# master.net
KiCad netlist of a schematic drawn in EAGLE
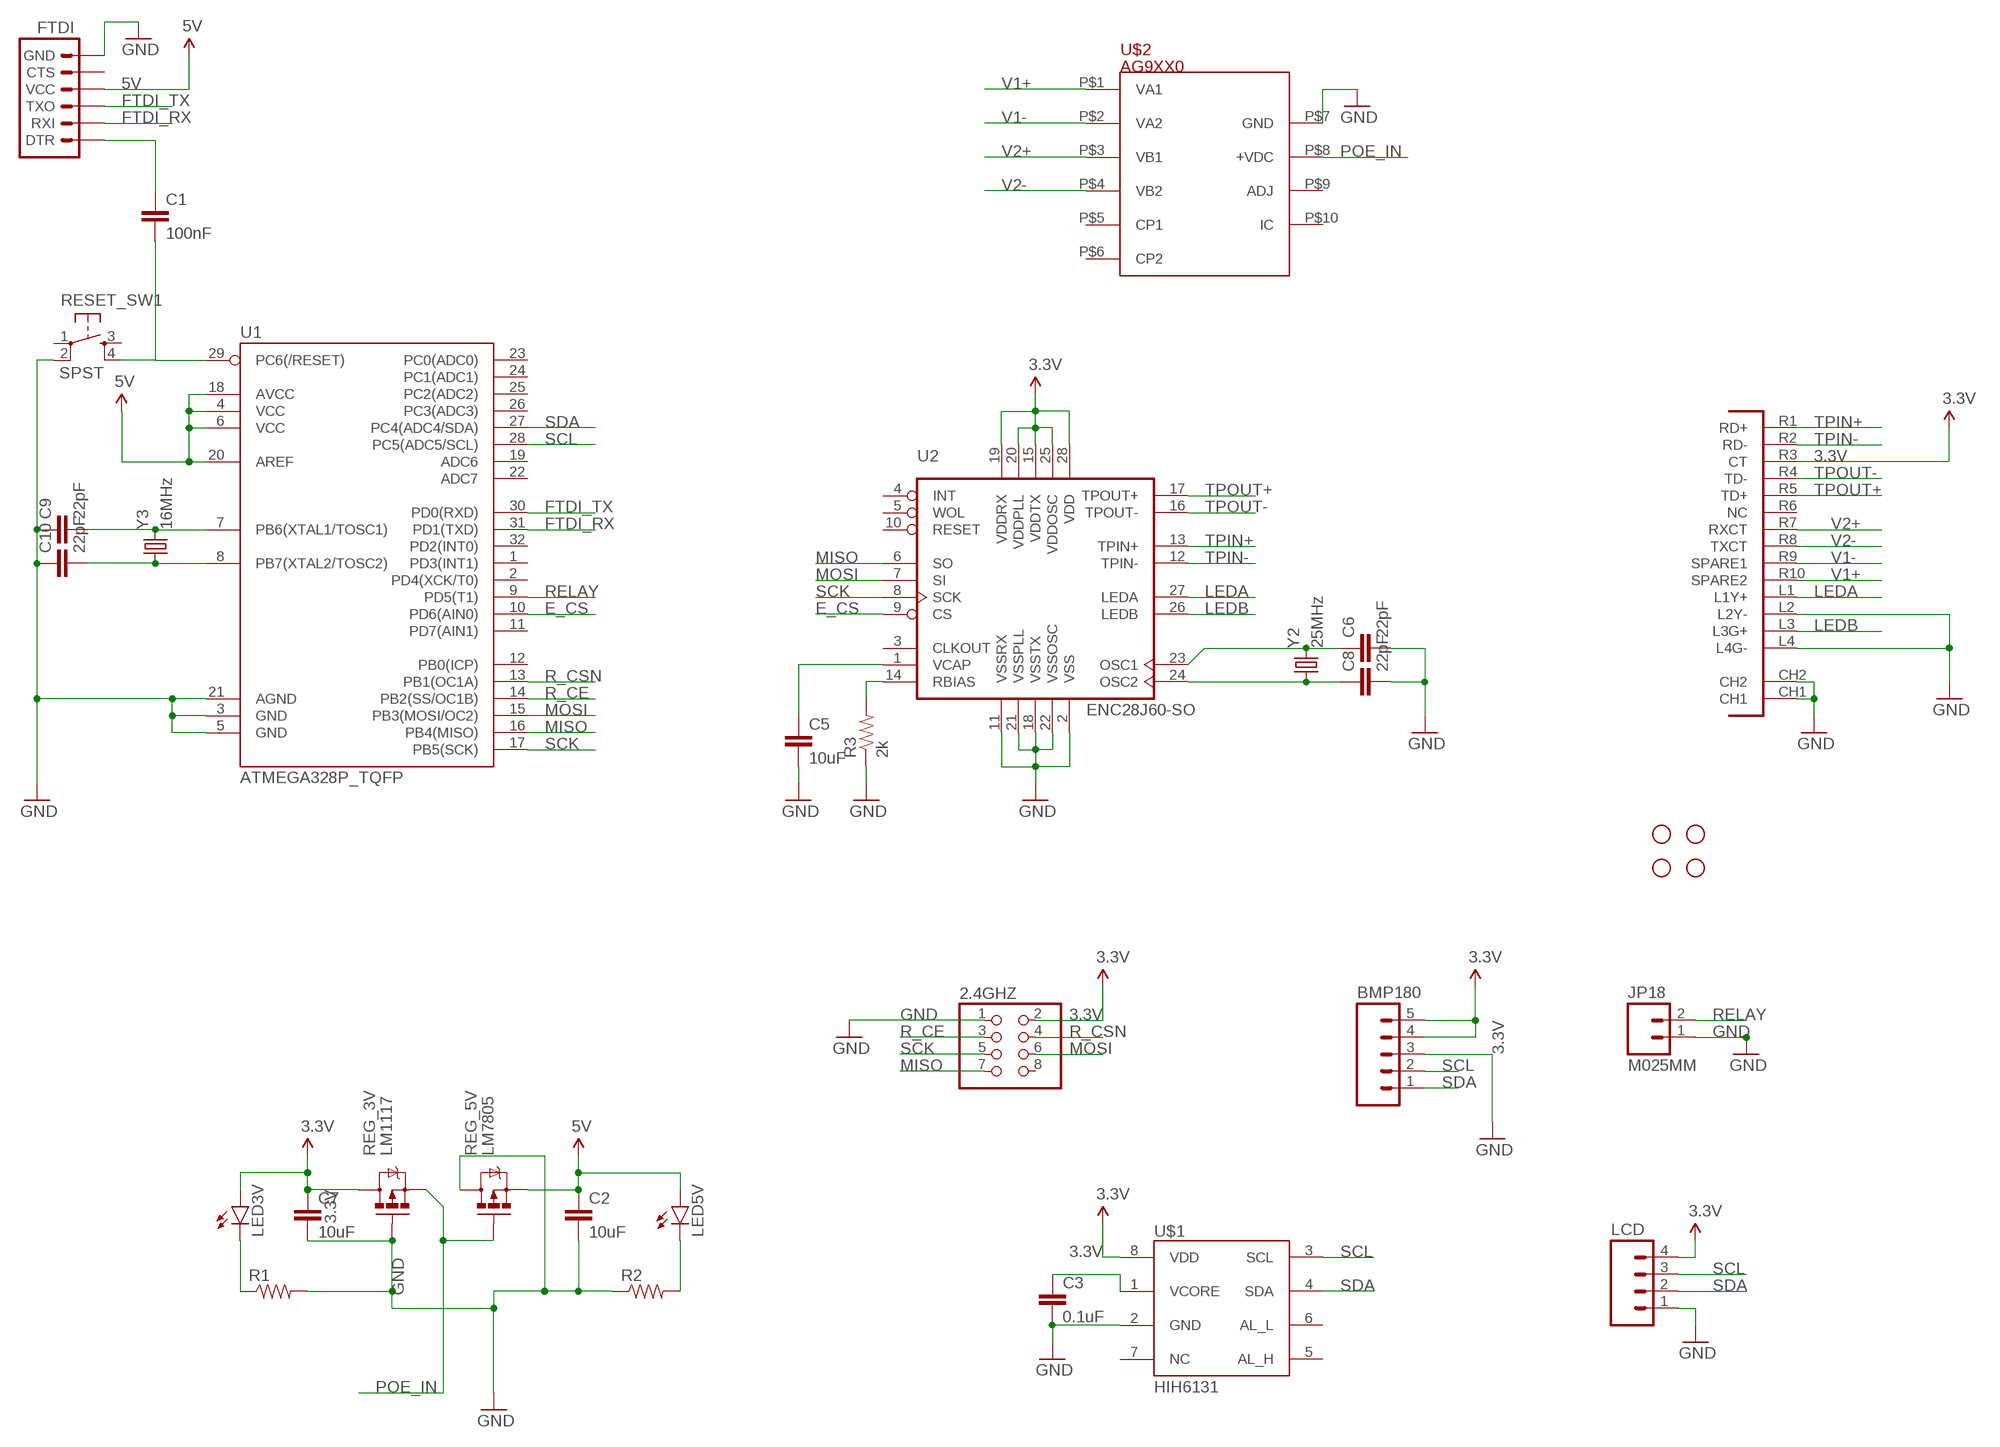
[diagram p0: schematic, sheet 1]

(export (version "E")
  (design (tool "Eeschema 10.0.6"))
  (components
    (comp (ref "2.4GHZ")
      (value "PINHD-2X4")
      (footprint "eagle-import:2X04")
      (libsource (lib "eagle-import") (part "PINHD-2X4"))
    )
    (comp (ref "BMP180")
      (value "M05PTH")
      (footprint "eagle-import:1X05")
      (libsource (lib "eagle-import") (part "M05PTH"))
    )
    (comp (ref "C1")
      (value "100nF")
      (footprint "eagle-import:CAP-PTH-SMALL")
      (libsource (lib "eagle-import") (part "CAPPTH"))
    )
    (comp (ref "C2")
      (value "10uF")
      (footprint "eagle-import:CAP-PTH-SMALL")
      (libsource (lib "eagle-import") (part "CAPPTH"))
    )
    (comp (ref "C3")
      (value "0.1uF")
      (footprint "eagle-import:CAP-PTH-SMALL")
      (libsource (lib "eagle-import") (part "CAPPTH"))
    )
    (comp (ref "C5")
      (value "10uF")
      (footprint "eagle-import:CAP-PTH-SMALL")
      (libsource (lib "eagle-import") (part "CAPPTH"))
    )
    (comp (ref "C6")
      (value "22pF")
      (footprint "eagle-import:CAP-PTH-SMALL")
      (libsource (lib "eagle-import") (part "CAPPTH"))
    )
    (comp (ref "C7")
      (value "10uF")
      (footprint "eagle-import:CAP-PTH-SMALL")
      (libsource (lib "eagle-import") (part "CAPPTH"))
    )
    (comp (ref "C8")
      (value "22pF")
      (footprint "eagle-import:CAP-PTH-SMALL")
      (libsource (lib "eagle-import") (part "CAPPTH"))
    )
    (comp (ref "C9")
      (value "22pF")
      (footprint "eagle-import:CAP-PTH-SMALL")
      (libsource (lib "eagle-import") (part "CAPPTH"))
    )
    (comp (ref "C10")
      (value "22pF")
      (footprint "eagle-import:CAP-PTH-SMALL")
      (libsource (lib "eagle-import") (part "CAPPTH"))
    )
    (comp (ref "FTDI")
      (value "ARDUINO_SERIAL_PROGRAMPTH")
      (footprint "eagle-import:1X06")
      (libsource (lib "eagle-import") (part "ARDUINO_SERIAL_PROGRAMPTH"))
    )
    (comp (ref "JP18")
      (value "M025MM")
      (footprint "eagle-import:SCREWTERMINAL-5MM-2")
      (libsource (lib "eagle-import") (part "M025MM"))
    )
    (comp (ref "LCD")
      (value "M04PTH")
      (footprint "eagle-import:1X04")
      (libsource (lib "eagle-import") (part "M04PTH"))
    )
    (comp (ref "LED3V")
      (value "LED3MM")
      (footprint "eagle-import:LED3MM")
      (libsource (lib "eagle-import") (part "LED3MM"))
    )
    (comp (ref "LED5V")
      (value "LED3MM")
      (footprint "eagle-import:LED3MM")
      (libsource (lib "eagle-import") (part "LED3MM"))
    )
    (comp (ref "R1")
      (value "RESISTORPTH-1/4W-VERT")
      (footprint "eagle-import:AXIAL-0.1")
      (libsource (lib "eagle-import") (part "RESISTORPTH-1/4W-VERT"))
    )
    (comp (ref "R2")
      (value "RESISTORPTH-1/4W-VERT")
      (footprint "eagle-import:AXIAL-0.1")
      (libsource (lib "eagle-import") (part "RESISTORPTH-1/4W-VERT"))
    )
    (comp (ref "R3")
      (value "2k")
      (footprint "eagle-import:AXIAL-0.1")
      (libsource (lib "eagle-import") (part "RESISTORPTH-1/4W-VERT"))
    )
    (comp (ref "REG_3V")
      (value "LM1117")
      (footprint "eagle-import:TO220V")
      (libsource (lib "eagle-import") (part "MOSFET-PCHANNELFQP27P06"))
    )
    (comp (ref "REG_5V")
      (value "LM7805")
      (footprint "eagle-import:TO220V")
      (libsource (lib "eagle-import") (part "MOSFET-PCHANNELFQP27P06"))
    )
    (comp (ref "RESET_SW1")
      (value "SPST")
      (footprint "eagle-import:TAC-SWITCH-PTH")
      (libsource (lib "eagle-import") (part "TACTILE-SWITCH-PTH"))
    )
    (comp (ref "STANDOFF1")
      (value "STAND-OFF")
      (footprint "eagle-import:STAND-OFF")
      (libsource (lib "eagle-import") (part "STAND-OFF"))
    )
    (comp (ref "STANDOFF2")
      (value "STAND-OFF")
      (footprint "eagle-import:STAND-OFF")
      (libsource (lib "eagle-import") (part "STAND-OFF"))
    )
    (comp (ref "STANDOFF3")
      (value "STAND-OFF")
      (footprint "eagle-import:STAND-OFF")
      (libsource (lib "eagle-import") (part "STAND-OFF"))
    )
    (comp (ref "STANDOFF4")
      (value "STAND-OFF")
      (footprint "eagle-import:STAND-OFF")
      (libsource (lib "eagle-import") (part "STAND-OFF"))
    )
    (comp (ref "U$1")
      (value "HIH6131")
      (footprint "eagle-import:SOIC8")
      (libsource (lib "eagle-import") (part "HIH6131"))
    )
    (comp (ref "U$2")
      (value "AG9XX0")
      (footprint "eagle-import:AG9000")
      (libsource (lib "eagle-import") (part "AG9XX0"))
    )
    (comp (ref "U$3")
      (value "POE-RJ45")
      (footprint "eagle-import:POE-RJ45")
      (libsource (lib "eagle-import") (part "POE-RJ45"))
    )
    (comp (ref "U1")
      (value "ATMEGA328P_TQFP")
      (footprint "eagle-import:TQFP32-08")
      (libsource (lib "eagle-import") (part "ATMEGA328P_TQFP"))
    )
    (comp (ref "U2")
      (value "ENC28J60-SO")
      (footprint "eagle-import:SO28W")
      (libsource (lib "eagle-import") (part "ENC28J60-SO"))
    )
    (comp (ref "Y2")
      (value "25MHz")
      (footprint "eagle-import:HC49US")
      (libsource (lib "eagle-import") (part "CRYSTALHC49US"))
    )
    (comp (ref "Y3")
      (value "16MHz")
      (footprint "eagle-import:HC49US")
      (libsource (lib "eagle-import") (part "CRYSTALHC49US"))
    )
  )
  (nets
    (net (code "1") (name "/E_CS") (class "Default")
      (node (ref "U1") (pin "10") (pinfunction "PD6(AIN0)_10") (pintype "bidirectional"))
      (node (ref "U2") (pin "9") (pinfunction "CS_9") (pintype "input"))
    )
    (net (code "2") (name "/FTDI_RX") (class "Default")
      (node (ref "FTDI") (pin "2") (pinfunction "RXI_2") (pintype "passive"))
      (node (ref "U1") (pin "31") (pinfunction "PD1(TXD)_31") (pintype "bidirectional"))
    )
    (net (code "3") (name "/FTDI_TX") (class "Default")
      (node (ref "FTDI") (pin "3") (pinfunction "TXO_3") (pintype "passive"))
      (node (ref "U1") (pin "30") (pinfunction "PD0(RXD)_30") (pintype "bidirectional"))
    )
    (net (code "4") (name "/LEDA") (class "Default")
      (node (ref "U$3") (pin "L1") (pinfunction "L1Y+_L1") (pintype "bidirectional"))
      (node (ref "U2") (pin "27") (pinfunction "LEDA_27") (pintype "output"))
    )
    (net (code "5") (name "/LEDB") (class "Default")
      (node (ref "U$3") (pin "L3") (pinfunction "L3G+_L3") (pintype "bidirectional"))
      (node (ref "U2") (pin "26") (pinfunction "LEDB_26") (pintype "output"))
    )
    (net (code "6") (name "/MISO") (class "Default")
      (node (ref "2.4GHZ") (pin "7") (pinfunction "7_7") (pintype "passive"))
      (node (ref "U1") (pin "16") (pinfunction "PB4(MISO)_16") (pintype "bidirectional"))
      (node (ref "U2") (pin "6") (pinfunction "SO_6") (pintype "output"))
    )
    (net (code "7") (name "/MOSI") (class "Default")
      (node (ref "2.4GHZ") (pin "6") (pinfunction "6_6") (pintype "passive"))
      (node (ref "U1") (pin "15") (pinfunction "PB3(MOSI/OC2)_15") (pintype "bidirectional"))
      (node (ref "U2") (pin "7") (pinfunction "SI_7") (pintype "input"))
    )
    (net (code "8") (name "/POE_IN") (class "Default")
      (node (ref "REG_3V") (pin "3") (pinfunction "S_3") (pintype "passive"))
      (node (ref "REG_5V") (pin "1") (pinfunction "G_1") (pintype "passive"))
      (node (ref "U$2") (pin "P$8") (pinfunction "+VDC_P$8") (pintype "power_in"))
    )
    (net (code "9") (name "/RELAY") (class "Default")
      (node (ref "JP18") (pin "2") (pinfunction "2_2") (pintype "passive"))
      (node (ref "U1") (pin "9") (pinfunction "PD5(T1)_9") (pintype "bidirectional"))
    )
    (net (code "10") (name "/R_CE") (class "Default")
      (node (ref "2.4GHZ") (pin "3") (pinfunction "3_3") (pintype "passive"))
      (node (ref "U1") (pin "14") (pinfunction "PB2(SS/OC1B)_14") (pintype "bidirectional"))
    )
    (net (code "11") (name "/R_CSN") (class "Default")
      (node (ref "2.4GHZ") (pin "4") (pinfunction "4_4") (pintype "passive"))
      (node (ref "U1") (pin "13") (pinfunction "PB1(OC1A)_13") (pintype "bidirectional"))
    )
    (net (code "12") (name "/SCK") (class "Default")
      (node (ref "2.4GHZ") (pin "5") (pinfunction "5_5") (pintype "passive"))
      (node (ref "U1") (pin "17") (pinfunction "PB5(SCK)_17") (pintype "bidirectional"))
      (node (ref "U2") (pin "8") (pinfunction "SCK_8") (pintype "input"))
    )
    (net (code "13") (name "/SCL") (class "Default")
      (node (ref "BMP180") (pin "2") (pinfunction "2_2") (pintype "passive"))
      (node (ref "LCD") (pin "3") (pinfunction "3_3") (pintype "passive"))
      (node (ref "U$1") (pin "3") (pinfunction "SCL_3") (pintype "bidirectional"))
      (node (ref "U1") (pin "28") (pinfunction "PC5(ADC5/SCL)_28") (pintype "bidirectional"))
    )
    (net (code "14") (name "/SDA") (class "Default")
      (node (ref "BMP180") (pin "1") (pinfunction "1_1") (pintype "passive"))
      (node (ref "LCD") (pin "2") (pinfunction "2_2") (pintype "passive"))
      (node (ref "U$1") (pin "4") (pinfunction "SDA_4") (pintype "bidirectional"))
      (node (ref "U1") (pin "27") (pinfunction "PC4(ADC4/SDA)_27") (pintype "bidirectional"))
    )
    (net (code "15") (name "/TPIN+") (class "Default")
      (node (ref "U$3") (pin "R1") (pinfunction "RD+_R1") (pintype "bidirectional"))
      (node (ref "U2") (pin "13") (pinfunction "TPIN+_13") (pintype "input"))
    )
    (net (code "16") (name "/TPIN-") (class "Default")
      (node (ref "U$3") (pin "R2") (pinfunction "RD-_R2") (pintype "bidirectional"))
      (node (ref "U2") (pin "12") (pinfunction "TPIN-_12") (pintype "input"))
    )
    (net (code "17") (name "/TPOUT+") (class "Default")
      (node (ref "U$3") (pin "R5") (pinfunction "TD+_R5") (pintype "bidirectional"))
      (node (ref "U2") (pin "17") (pinfunction "TPOUT+_17") (pintype "output"))
    )
    (net (code "18") (name "/TPOUT-") (class "Default")
      (node (ref "U$3") (pin "R4") (pinfunction "TD-_R4") (pintype "bidirectional"))
      (node (ref "U2") (pin "16") (pinfunction "TPOUT-_16") (pintype "output"))
    )
    (net (code "19") (name "/V1+") (class "Default")
      (node (ref "U$2") (pin "P$1") (pinfunction "VA1_P$1") (pintype "input"))
      (node (ref "U$3") (pin "R10") (pinfunction "SPARE2_R10") (pintype "bidirectional"))
    )
    (net (code "20") (name "/V1-") (class "Default")
      (node (ref "U$2") (pin "P$2") (pinfunction "VA2_P$2") (pintype "input"))
      (node (ref "U$3") (pin "R9") (pinfunction "SPARE1_R9") (pintype "bidirectional"))
    )
    (net (code "21") (name "/V2+") (class "Default")
      (node (ref "U$2") (pin "P$3") (pinfunction "VB1_P$3") (pintype "input"))
      (node (ref "U$3") (pin "R7") (pinfunction "RXCT_R7") (pintype "bidirectional"))
    )
    (net (code "22") (name "/V2-") (class "Default")
      (node (ref "U$2") (pin "P$4") (pinfunction "VB2_P$4") (pintype "input"))
      (node (ref "U$3") (pin "R8") (pinfunction "TXCT_R8") (pintype "bidirectional"))
    )
    (net (code "23") (name "3.3V") (class "Default")
      (node (ref "2.4GHZ") (pin "2") (pinfunction "2_2") (pintype "passive"))
      (node (ref "BMP180") (pin "4") (pinfunction "4_4") (pintype "passive"))
      (node (ref "BMP180") (pin "5") (pinfunction "5_5") (pintype "passive"))
      (node (ref "C7") (pin "1") (pinfunction "1_1") (pintype "passive"))
      (node (ref "LCD") (pin "4") (pinfunction "4_4") (pintype "passive"))
      (node (ref "LED3V") (pin "A") (pinfunction "A_A") (pintype "passive"))
      (node (ref "REG_3V") (pin "2") (pinfunction "D_2") (pintype "passive"))
      (node (ref "U$1") (pin "8") (pinfunction "VDD_8") (pintype "bidirectional"))
      (node (ref "U$3") (pin "R3") (pinfunction "CT_R3") (pintype "bidirectional"))
      (node (ref "U2") (pin "15") (pinfunction "VDDTX_15") (pintype "power_in"))
      (node (ref "U2") (pin "19") (pinfunction "VDDRX_19") (pintype "power_in"))
      (node (ref "U2") (pin "20") (pinfunction "VDDPLL_20") (pintype "power_in"))
      (node (ref "U2") (pin "25") (pinfunction "VDDOSC_25") (pintype "power_in"))
      (node (ref "U2") (pin "28") (pinfunction "VDD_28") (pintype "power_in"))
    )
    (net (code "24") (name "5V") (class "Default")
      (node (ref "C2") (pin "1") (pinfunction "1_1") (pintype "passive"))
      (node (ref "FTDI") (pin "4") (pinfunction "VCC_4") (pintype "passive"))
      (node (ref "LED5V") (pin "A") (pinfunction "A_A") (pintype "passive"))
      (node (ref "REG_5V") (pin "3") (pinfunction "S_3") (pintype "passive"))
      (node (ref "U1") (pin "18") (pinfunction "AVCC_18") (pintype "bidirectional"))
      (node (ref "U1") (pin "20") (pinfunction "AREF_20") (pintype "bidirectional"))
      (node (ref "U1") (pin "4") (pinfunction "VCC_4") (pintype "bidirectional"))
      (node (ref "U1") (pin "6") (pinfunction "VCC_6") (pintype "bidirectional"))
    )
    (net (code "25") (name "GND") (class "Default")
      (node (ref "2.4GHZ") (pin "1") (pinfunction "1_1") (pintype "passive"))
      (node (ref "BMP180") (pin "3") (pinfunction "3_3") (pintype "passive"))
      (node (ref "C10") (pin "1") (pinfunction "1_1") (pintype "passive"))
      (node (ref "C2") (pin "2") (pinfunction "2_2") (pintype "passive"))
      (node (ref "C3") (pin "2") (pinfunction "2_2") (pintype "passive"))
      (node (ref "C5") (pin "2") (pinfunction "2_2") (pintype "passive"))
      (node (ref "C6") (pin "2") (pinfunction "2_2") (pintype "passive"))
      (node (ref "C7") (pin "2") (pinfunction "2_2") (pintype "passive"))
      (node (ref "C8") (pin "2") (pinfunction "2_2") (pintype "passive"))
      (node (ref "C9") (pin "1") (pinfunction "1_1") (pintype "passive"))
      (node (ref "FTDI") (pin "6") (pinfunction "GND_6") (pintype "passive"))
      (node (ref "JP18") (pin "1") (pinfunction "1_1") (pintype "passive"))
      (node (ref "LCD") (pin "1") (pinfunction "1_1") (pintype "passive"))
      (node (ref "R1") (pin "P$2") (pinfunction "2_P$2") (pintype "passive"))
      (node (ref "R2") (pin "P$1") (pinfunction "1_P$1") (pintype "passive"))
      (node (ref "R3") (pin "P$1") (pinfunction "1_P$1") (pintype "passive"))
      (node (ref "REG_3V") (pin "1") (pinfunction "G_1") (pintype "passive"))
      (node (ref "REG_5V") (pin "2") (pinfunction "D_2") (pintype "passive"))
      (node (ref "RESET_SW1") (pin "2") (pinfunction "2_2") (pintype "passive"))
      (node (ref "U$1") (pin "2") (pinfunction "GND_2") (pintype "bidirectional"))
      (node (ref "U$2") (pin "P$7") (pinfunction "GND_P$7") (pintype "power_in"))
      (node (ref "U$3") (pin "CH1") (pinfunction "CH1_CH1") (pintype "bidirectional"))
      (node (ref "U$3") (pin "CH2") (pinfunction "CH2_CH2") (pintype "bidirectional"))
      (node (ref "U$3") (pin "L2") (pinfunction "L2Y-_L2") (pintype "bidirectional"))
      (node (ref "U$3") (pin "L4") (pinfunction "L4G-_L4") (pintype "bidirectional"))
      (node (ref "U1") (pin "21") (pinfunction "AGND_21") (pintype "bidirectional"))
      (node (ref "U1") (pin "3") (pinfunction "GND_3") (pintype "bidirectional"))
      (node (ref "U1") (pin "5") (pinfunction "GND_5") (pintype "bidirectional"))
      (node (ref "U2") (pin "11") (pinfunction "VSSRX_11") (pintype "power_in"))
      (node (ref "U2") (pin "18") (pinfunction "VSSTX_18") (pintype "power_in"))
      (node (ref "U2") (pin "2") (pinfunction "VSS_2") (pintype "power_in"))
      (node (ref "U2") (pin "21") (pinfunction "VSSPLL_21") (pintype "power_in"))
      (node (ref "U2") (pin "22") (pinfunction "VSSOSC_22") (pintype "power_in"))
    )
    (net (code "26") (name "Net-(FTDI-DTR)") (class "Default")
      (node (ref "C1") (pin "1") (pinfunction "1_1") (pintype "passive"))
      (node (ref "FTDI") (pin "1") (pinfunction "DTR_1") (pintype "passive"))
    )
    (net (code "27") (name "Net-(LED3V-C)") (class "Default")
      (node (ref "LED3V") (pin "K") (pinfunction "C_K") (pintype "passive"))
      (node (ref "R1") (pin "P$1") (pinfunction "1_P$1") (pintype "passive"))
    )
    (net (code "28") (name "Net-(LED5V-C)") (class "Default")
      (node (ref "LED5V") (pin "K") (pinfunction "C_K") (pintype "passive"))
      (node (ref "R2") (pin "P$2") (pinfunction "2_P$2") (pintype "passive"))
    )
    (net (code "29") (name "Net-(R3-2)") (class "Default")
      (node (ref "R3") (pin "P$2") (pinfunction "2_P$2") (pintype "passive"))
      (node (ref "U2") (pin "14") (pinfunction "RBIAS_14") (pintype "passive"))
    )
    (net (code "30") (name "Net-(U$1-VCORE)") (class "Default")
      (node (ref "C3") (pin "1") (pinfunction "1_1") (pintype "passive"))
      (node (ref "U$1") (pin "1") (pinfunction "VCORE_1") (pintype "bidirectional"))
    )
    (net (code "31") (name "Net-(U1-PB6(XTAL1{slash}TOSC1))") (class "Default")
      (node (ref "C9") (pin "2") (pinfunction "2_2") (pintype "passive"))
      (node (ref "U1") (pin "7") (pinfunction "PB6(XTAL1/TOSC1)_7") (pintype "bidirectional"))
      (node (ref "Y3") (pin "2") (pinfunction "2_2") (pintype "passive"))
    )
    (net (code "32") (name "Net-(U1-PB7(XTAL2{slash}TOSC2))") (class "Default")
      (node (ref "C10") (pin "2") (pinfunction "2_2") (pintype "passive"))
      (node (ref "U1") (pin "8") (pinfunction "PB7(XTAL2/TOSC2)_8") (pintype "bidirectional"))
      (node (ref "Y3") (pin "1") (pinfunction "1_1") (pintype "passive"))
    )
    (net (code "33") (name "Net-(U1-PC6({slash}RESET))") (class "Default")
      (node (ref "C1") (pin "2") (pinfunction "2_2") (pintype "passive"))
      (node (ref "RESET_SW1") (pin "4") (pinfunction "4_4") (pintype "passive"))
      (node (ref "U1") (pin "29") (pinfunction "PC6(/RESET)_29") (pintype "bidirectional"))
    )
    (net (code "34") (name "Net-(U2-OSC1)") (class "Default")
      (node (ref "C6") (pin "1") (pinfunction "1_1") (pintype "passive"))
      (node (ref "U2") (pin "23") (pinfunction "OSC1_23") (pintype "input"))
      (node (ref "Y2") (pin "2") (pinfunction "2_2") (pintype "passive"))
    )
    (net (code "35") (name "Net-(U2-OSC2)") (class "Default")
      (node (ref "C8") (pin "1") (pinfunction "1_1") (pintype "passive"))
      (node (ref "U2") (pin "24") (pinfunction "OSC2_24") (pintype "output"))
      (node (ref "Y2") (pin "1") (pinfunction "1_1") (pintype "passive"))
    )
    (net (code "36") (name "Net-(U2-VCAP)") (class "Default")
      (node (ref "C5") (pin "1") (pinfunction "1_1") (pintype "passive"))
      (node (ref "U2") (pin "1") (pinfunction "VCAP_1") (pintype "power_in"))
    )
    (net (code "37") (name "unconnected-(2.4GHZ-Pad8)") (class "Default")
      (node (ref "2.4GHZ") (pin "8") (pinfunction "8_8") (pintype "passive"))
    )
    (net (code "38") (name "unconnected-(FTDI-CTS-Pad5)") (class "Default")
      (node (ref "FTDI") (pin "5") (pinfunction "CTS_5") (pintype "passive"))
    )
    (net (code "39") (name "unconnected-(RESET_SW1-Pad1)") (class "Default")
      (node (ref "RESET_SW1") (pin "1") (pinfunction "1_1") (pintype "passive"))
    )
    (net (code "40") (name "unconnected-(RESET_SW1-Pad3)") (class "Default")
      (node (ref "RESET_SW1") (pin "3") (pinfunction "3_3") (pintype "passive"))
    )
    (net (code "41") (name "unconnected-(U$1-AL_H-Pad5)") (class "Default")
      (node (ref "U$1") (pin "5") (pinfunction "AL_H_5") (pintype "bidirectional"))
    )
    (net (code "42") (name "unconnected-(U$1-AL_L-Pad6)") (class "Default")
      (node (ref "U$1") (pin "6") (pinfunction "AL_L_6") (pintype "bidirectional"))
    )
    (net (code "43") (name "unconnected-(U$1-NC-Pad7)") (class "Default")
      (node (ref "U$1") (pin "7") (pinfunction "NC_7") (pintype "bidirectional"))
    )
    (net (code "44") (name "unconnected-(U$2-ADJ-PadP$9)") (class "Default")
      (node (ref "U$2") (pin "P$9") (pinfunction "ADJ_P$9") (pintype "passive"))
    )
    (net (code "45") (name "unconnected-(U$2-CP1-PadP$5)") (class "Default")
      (node (ref "U$2") (pin "P$5") (pinfunction "CP1_P$5") (pintype "input"))
    )
    (net (code "46") (name "unconnected-(U$2-CP2-PadP$6)") (class "Default")
      (node (ref "U$2") (pin "P$6") (pinfunction "CP2_P$6") (pintype "input"))
    )
    (net (code "47") (name "unconnected-(U$2-IC-PadP$10)") (class "Default")
      (node (ref "U$2") (pin "P$10") (pinfunction "IC_P$10") (pintype "no_connect"))
    )
    (net (code "48") (name "unconnected-(U$3-NC-PadR6)") (class "Default")
      (node (ref "U$3") (pin "R6") (pinfunction "NC_R6") (pintype "bidirectional"))
    )
    (net (code "49") (name "unconnected-(U1-ADC6-Pad19)") (class "Default")
      (node (ref "U1") (pin "19") (pinfunction "ADC6_19") (pintype "bidirectional"))
    )
    (net (code "50") (name "unconnected-(U1-ADC7-Pad22)") (class "Default")
      (node (ref "U1") (pin "22") (pinfunction "ADC7_22") (pintype "bidirectional"))
    )
    (net (code "51") (name "unconnected-(U1-PB0(ICP)-Pad12)") (class "Default")
      (node (ref "U1") (pin "12") (pinfunction "PB0(ICP)_12") (pintype "bidirectional"))
    )
    (net (code "52") (name "unconnected-(U1-PC0(ADC0)-Pad23)") (class "Default")
      (node (ref "U1") (pin "23") (pinfunction "PC0(ADC0)_23") (pintype "bidirectional"))
    )
    (net (code "53") (name "unconnected-(U1-PC1(ADC1)-Pad24)") (class "Default")
      (node (ref "U1") (pin "24") (pinfunction "PC1(ADC1)_24") (pintype "bidirectional"))
    )
    (net (code "54") (name "unconnected-(U1-PC2(ADC2)-Pad25)") (class "Default")
      (node (ref "U1") (pin "25") (pinfunction "PC2(ADC2)_25") (pintype "bidirectional"))
    )
    (net (code "55") (name "unconnected-(U1-PC3(ADC3)-Pad26)") (class "Default")
      (node (ref "U1") (pin "26") (pinfunction "PC3(ADC3)_26") (pintype "bidirectional"))
    )
    (net (code "56") (name "unconnected-(U1-PD2(INT0)-Pad32)") (class "Default")
      (node (ref "U1") (pin "32") (pinfunction "PD2(INT0)_32") (pintype "bidirectional"))
    )
    (net (code "57") (name "unconnected-(U1-PD3(INT1)-Pad1)") (class "Default")
      (node (ref "U1") (pin "1") (pinfunction "PD3(INT1)_1") (pintype "bidirectional"))
    )
    (net (code "58") (name "unconnected-(U1-PD4(XCK{slash}T0)-Pad2)") (class "Default")
      (node (ref "U1") (pin "2") (pinfunction "PD4(XCK/T0)_2") (pintype "bidirectional"))
    )
    (net (code "59") (name "unconnected-(U1-PD7(AIN1)-Pad11)") (class "Default")
      (node (ref "U1") (pin "11") (pinfunction "PD7(AIN1)_11") (pintype "bidirectional"))
    )
    (net (code "60") (name "unconnected-(U2-CLKOUT-Pad3)") (class "Default")
      (node (ref "U2") (pin "3") (pinfunction "CLKOUT_3") (pintype "output"))
    )
    (net (code "61") (name "unconnected-(U2-INT-Pad4)") (class "Default")
      (node (ref "U2") (pin "4") (pinfunction "INT_4") (pintype "output"))
    )
    (net (code "62") (name "unconnected-(U2-RESET-Pad10)") (class "Default")
      (node (ref "U2") (pin "10") (pinfunction "RESET_10") (pintype "input"))
    )
    (net (code "63") (name "unconnected-(U2-WOL-Pad5)") (class "Default")
      (node (ref "U2") (pin "5") (pinfunction "WOL_5") (pintype "output"))
    )
  )
)
